# SCH_RELAY.net
KiCad netlist of a schematic drawn in Altium Designer
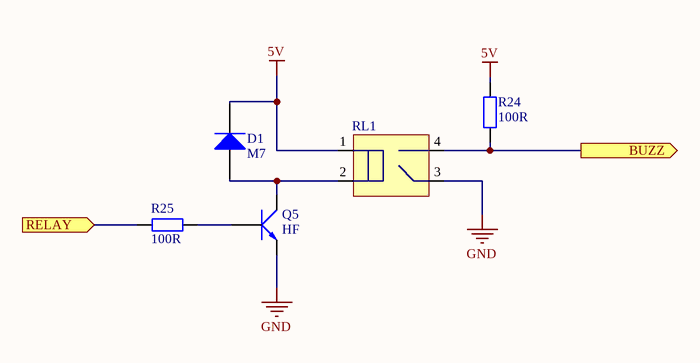
[diagram p0: SCH_RELAY.SchDoc]

(export (version "E")
  (design (tool "Eeschema 10.0.6"))
  (components
    (comp (ref "D1")
      (value "M7")
      (footprint "DIODE SMA")
      (description "Dán")
      (libsource (lib "Altium_Lib_by_KhueNguyenCreator") (part "Diode M7 ( 4007 )"))
    )
    (comp (ref "Q5")
      (value "HF")
      (footprint "SOT23")
      (description "NPN transistor")
      (libsource (lib "Altium_Lib_by_KhueNguyenCreator") (part "C1815 HF SMD"))
    )
    (comp (ref "R24")
      (value "100R")
      (footprint "tro smd 0603")
      (description "Dán")
      (libsource (lib "Altium_Lib_by_KhueNguyenCreator") (part "Tro 0603 5% 100R"))
    )
    (comp (ref "R25")
      (value "100R")
      (footprint "tro smd 0805")
      (description "Dán")
      (libsource (lib "Altium_Lib_by_KhueNguyenCreator") (part "Tro 0805 5% 100R"))
    )
    (comp (ref "RL1")
      (value "~")
      (footprint "Relay 4 chan HF46F")
      (description "Relay 4 chan HF46F")
      (libsource (lib "Altium_Lib_by_KhueNguyenCreator") (part "Relay 4 chan HF46F"))
    )
  )
  (nets
    (net (code "1") (name "/BUZZ") (class "Default")
      (node (ref "R24") (pin "1") (pinfunction "1_1") (pintype "passive"))
      (node (ref "RL1") (pin "4") (pinfunction "AC/DC_4") (pintype "passive"))
    )
    (net (code "2") (name "/RELAY") (class "Default")
      (node (ref "R25") (pin "1") (pinfunction "1_1") (pintype "passive"))
    )
    (net (code "3") (name "5V") (class "Default")
      (node (ref "D1") (pin "2") (pinfunction "K_2") (pintype "passive"))
      (node (ref "R24") (pin "2") (pinfunction "2_2") (pintype "passive"))
      (node (ref "RL1") (pin "1") (pintype "passive"))
    )
    (net (code "4") (name "GND") (class "Default")
      (node (ref "Q5") (pin "2") (pinfunction "E_2") (pintype "passive"))
      (node (ref "RL1") (pin "3") (pinfunction "AC/DC_3") (pintype "passive"))
    )
    (net (code "5") (name "Net-(D1-A)") (class "Default")
      (node (ref "D1") (pin "1") (pinfunction "A_1") (pintype "passive"))
      (node (ref "Q5") (pin "3") (pinfunction "C_3") (pintype "passive"))
      (node (ref "RL1") (pin "2") (pintype "passive"))
    )
    (net (code "6") (name "Net-(Q5-B)") (class "Default")
      (node (ref "Q5") (pin "1") (pinfunction "B_1") (pintype "passive"))
      (node (ref "R25") (pin "2") (pinfunction "2_2") (pintype "passive"))
    )
  )
)
